# ps.net
KiCad netlist of a schematic drawn in EAGLE
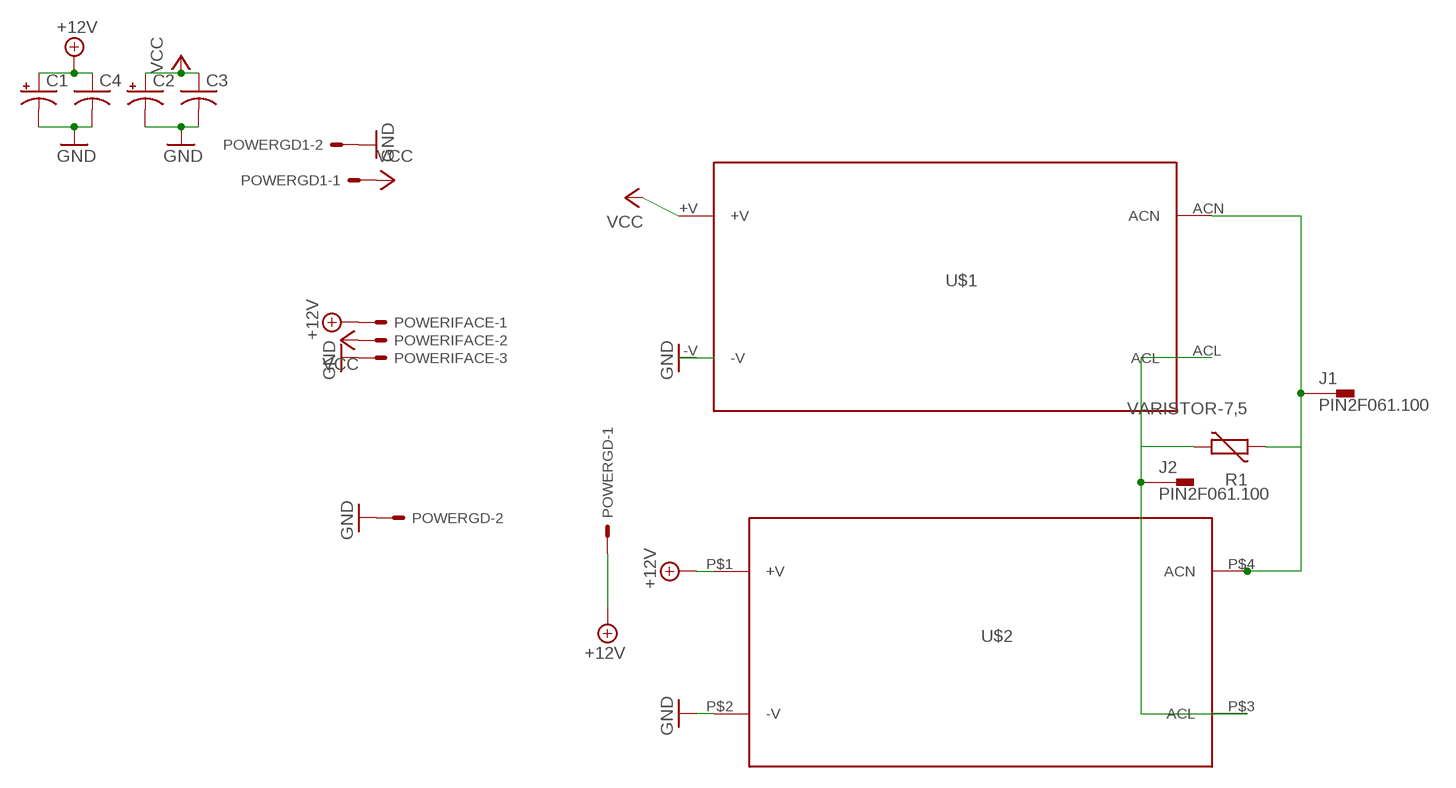
[diagram p0: schematic, sheet 1]

(export (version "E")
  (design (tool "Eeschema 10.0.6"))
  (components
    (comp (ref "C1")
      (value "CPOL-USE5-13")
      (footprint "eagle-import:E5-13")
      (libsource (lib "eagle-import") (part "CPOL-USE5-13"))
    )
    (comp (ref "C2")
      (value "CPOL-USE5-13")
      (footprint "eagle-import:E5-13")
      (libsource (lib "eagle-import") (part "CPOL-USE5-13"))
    )
    (comp (ref "C3")
      (value "C-US050-050X075")
      (footprint "eagle-import:C050-050X075")
      (libsource (lib "eagle-import") (part "C-US050-050X075"))
    )
    (comp (ref "C4")
      (value "C-US050-050X075")
      (footprint "eagle-import:C050-050X075")
      (libsource (lib "eagle-import") (part "C-US050-050X075"))
    )
    (comp (ref "J1")
      (value "PIN2F061.100")
      (footprint "eagle-import:F061.100")
      (libsource (lib "eagle-import") (part "PIN2F061.100"))
    )
    (comp (ref "J2")
      (value "PIN2F061.100")
      (footprint "eagle-import:F061.100")
      (libsource (lib "eagle-import") (part "PIN2F061.100"))
    )
    (comp (ref "POWERGD")
      (value "KK-156-2")
      (footprint "eagle-import:KK-156-2")
      (libsource (lib "eagle-import") (part "KK-156-2"))
    )
    (comp (ref "POWERGD1")
      (value "KK-156-2")
      (footprint "eagle-import:KK-156-2")
      (libsource (lib "eagle-import") (part "KK-156-2"))
    )
    (comp (ref "POWERIFACE")
      (value "KK-156-3")
      (footprint "eagle-import:KK-156-3")
      (libsource (lib "eagle-import") (part "KK-156-3"))
    )
    (comp (ref "R1")
      (value "VARISTOR-7,5")
      (footprint "eagle-import:R-7,5")
      (libsource (lib "eagle-import") (part "VARISTOR-7,5"))
    )
    (comp (ref "U$1")
      (value "IRM-05-05")
      (footprint "eagle-import:IRM-05-05")
      (libsource (lib "eagle-import") (part "IRM-05-05"))
    )
    (comp (ref "U$2")
      (value "IRM-60-12")
      (footprint "eagle-import:IRM-60-12")
      (libsource (lib "eagle-import") (part "IRM-60-12"))
    )
  )
  (nets
    (net (code "1") (name "+12V") (class "Default")
      (node (ref "C1") (pin "+") (pinfunction "+_+") (pintype "passive"))
      (node (ref "C4") (pin "1") (pinfunction "1_1") (pintype "passive"))
      (node (ref "POWERGD") (pin "1") (pinfunction "S_1") (pintype "passive"))
      (node (ref "POWERIFACE") (pin "1") (pinfunction "S_1") (pintype "passive"))
      (node (ref "U$2") (pin "P$1") (pinfunction "+V_P$1") (pintype "bidirectional"))
    )
    (net (code "2") (name "GND") (class "Default")
      (node (ref "C1") (pin "-") (pinfunction "-_-") (pintype "passive"))
      (node (ref "C2") (pin "-") (pinfunction "-_-") (pintype "passive"))
      (node (ref "C3") (pin "2") (pinfunction "2_2") (pintype "passive"))
      (node (ref "C4") (pin "2") (pinfunction "2_2") (pintype "passive"))
      (node (ref "POWERGD") (pin "2") (pinfunction "S_2") (pintype "passive"))
      (node (ref "POWERGD1") (pin "2") (pinfunction "S_2") (pintype "passive"))
      (node (ref "POWERIFACE") (pin "3") (pinfunction "S_3") (pintype "passive"))
      (node (ref "U$1") (pin "-V") (pinfunction "-V_-V") (pintype "bidirectional"))
      (node (ref "U$2") (pin "P$2") (pinfunction "-V_P$2") (pintype "bidirectional"))
    )
    (net (code "3") (name "Net-(U$2-ACL)") (class "Default")
      (node (ref "J2") (pin "A1") (pinfunction "1_A1") (pintype "passive"))
      (node (ref "J2") (pin "A2") (pinfunction "1_A2") (pintype "passive"))
      (node (ref "R1") (pin "1") (pinfunction "1_1") (pintype "passive"))
      (node (ref "U$1") (pin "ACL") (pinfunction "ACL_ACL") (pintype "bidirectional"))
      (node (ref "U$2") (pin "P$3") (pinfunction "ACL_P$3") (pintype "bidirectional"))
    )
    (net (code "4") (name "Net-(U$2-ACN)") (class "Default")
      (node (ref "J1") (pin "A1") (pinfunction "1_A1") (pintype "passive"))
      (node (ref "J1") (pin "A2") (pinfunction "1_A2") (pintype "passive"))
      (node (ref "R1") (pin "2") (pinfunction "2_2") (pintype "passive"))
      (node (ref "U$1") (pin "ACN") (pinfunction "ACN_ACN") (pintype "bidirectional"))
      (node (ref "U$2") (pin "P$4") (pinfunction "ACN_P$4") (pintype "bidirectional"))
    )
    (net (code "5") (name "VCC") (class "Default")
      (node (ref "C2") (pin "+") (pinfunction "+_+") (pintype "passive"))
      (node (ref "C3") (pin "1") (pinfunction "1_1") (pintype "passive"))
      (node (ref "POWERGD1") (pin "1") (pinfunction "S_1") (pintype "passive"))
      (node (ref "POWERIFACE") (pin "2") (pinfunction "S_2") (pintype "passive"))
      (node (ref "U$1") (pin "+V") (pinfunction "+V_+V") (pintype "bidirectional"))
    )
  )
)
